# Shield.net
KiCad netlist of a schematic drawn in Altium Designer
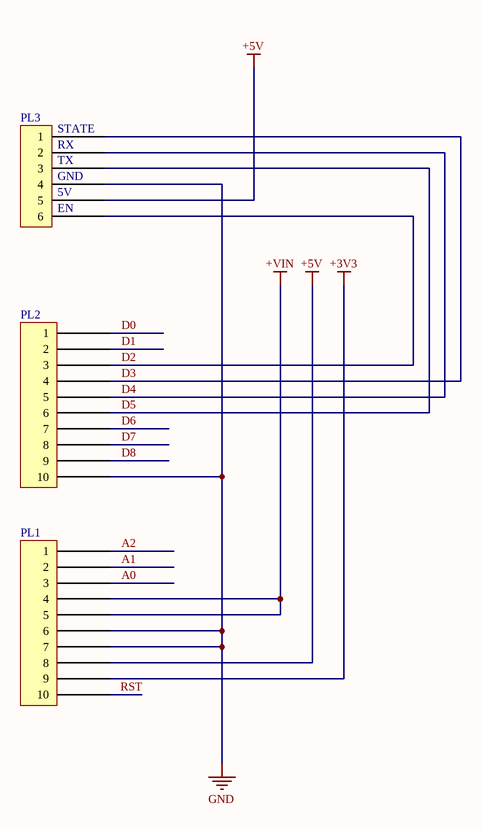
[diagram p0: Shield.SchDoc]

(export (version "E")
  (design (tool "Eeschema 10.0.6"))
  (components
    (comp (ref "PL1")
      (value "10-pin Male Header 2.54mm")
      (footprint "10-pin 2.54mm header")
      (description "10 Positions Header Connector 0.100\" (2.54mm) Through Hole Gold")
      (libsource (lib "ON Development Vault") (part "10-pin header"))
    )
    (comp (ref "PL2")
      (value "10-pin Male Header 2.54mm")
      (footprint "10-pin 2.54mm header")
      (description "10 Positions Header Connector 0.100\" (2.54mm) Through Hole Gold")
      (libsource (lib "ON Development Vault") (part "10-pin header"))
    )
    (comp (ref "PL3")
      (value "6-pin 2.54mm female right angle")
      (footprint "6-pin 2.54mm header - female right angle")
      (description "Pin Header 6-pin 2.54mm female right angle")
      (libsource (lib "ON Development Vault") (part "6-pin header"))
    )
  )
  (nets
    (net (code "1") (name "+3V3") (class "Default")
      (node (ref "PL1") (pin "9") (pinfunction "9_9") (pintype "passive"))
    )
    (net (code "2") (name "+5V") (class "Default")
      (node (ref "PL1") (pin "8") (pinfunction "8_8") (pintype "passive"))
      (node (ref "PL3") (pin "5") (pinfunction "5_5") (pintype "passive"))
    )
    (net (code "3") (name "+VIN") (class "Default")
      (node (ref "PL1") (pin "4") (pinfunction "4_4") (pintype "passive"))
      (node (ref "PL1") (pin "5") (pinfunction "5_5") (pintype "passive"))
    )
    (net (code "4") (name "/A0") (class "Default")
      (node (ref "PL1") (pin "3") (pinfunction "3_3") (pintype "passive"))
    )
    (net (code "5") (name "/A1") (class "Default")
      (node (ref "PL1") (pin "2") (pinfunction "2_2") (pintype "passive"))
    )
    (net (code "6") (name "/A2") (class "Default")
      (node (ref "PL1") (pin "1") (pinfunction "1_1") (pintype "passive"))
    )
    (net (code "7") (name "/D0") (class "Default")
      (node (ref "PL2") (pin "1") (pinfunction "1_1") (pintype "passive"))
    )
    (net (code "8") (name "/D1") (class "Default")
      (node (ref "PL2") (pin "2") (pinfunction "2_2") (pintype "passive"))
    )
    (net (code "9") (name "/D2") (class "Default")
      (node (ref "PL2") (pin "3") (pinfunction "3_3") (pintype "passive"))
      (node (ref "PL3") (pin "6") (pinfunction "6_6") (pintype "passive"))
    )
    (net (code "10") (name "/D3") (class "Default")
      (node (ref "PL2") (pin "4") (pinfunction "4_4") (pintype "passive"))
      (node (ref "PL3") (pin "1") (pinfunction "1_1") (pintype "passive"))
    )
    (net (code "11") (name "/D4") (class "Default")
      (node (ref "PL2") (pin "5") (pinfunction "5_5") (pintype "passive"))
      (node (ref "PL3") (pin "2") (pinfunction "2_2") (pintype "passive"))
    )
    (net (code "12") (name "/D5") (class "Default")
      (node (ref "PL2") (pin "6") (pinfunction "6_6") (pintype "passive"))
      (node (ref "PL3") (pin "3") (pinfunction "3_3") (pintype "passive"))
    )
    (net (code "13") (name "/D6") (class "Default")
      (node (ref "PL2") (pin "7") (pinfunction "7_7") (pintype "passive"))
    )
    (net (code "14") (name "/D7") (class "Default")
      (node (ref "PL2") (pin "8") (pinfunction "8_8") (pintype "passive"))
    )
    (net (code "15") (name "/D8") (class "Default")
      (node (ref "PL2") (pin "9") (pinfunction "9_9") (pintype "passive"))
    )
    (net (code "16") (name "/RST") (class "Default")
      (node (ref "PL1") (pin "10") (pinfunction "10_10") (pintype "passive"))
    )
    (net (code "17") (name "GND") (class "Default")
      (node (ref "PL1") (pin "6") (pinfunction "6_6") (pintype "passive"))
      (node (ref "PL1") (pin "7") (pinfunction "7_7") (pintype "passive"))
      (node (ref "PL2") (pin "10") (pinfunction "10_10") (pintype "passive"))
      (node (ref "PL3") (pin "4") (pinfunction "4_4") (pintype "passive"))
    )
  )
)
